# Lakota_PCB.net
KiCad netlist of a schematic drawn in Altium Designer
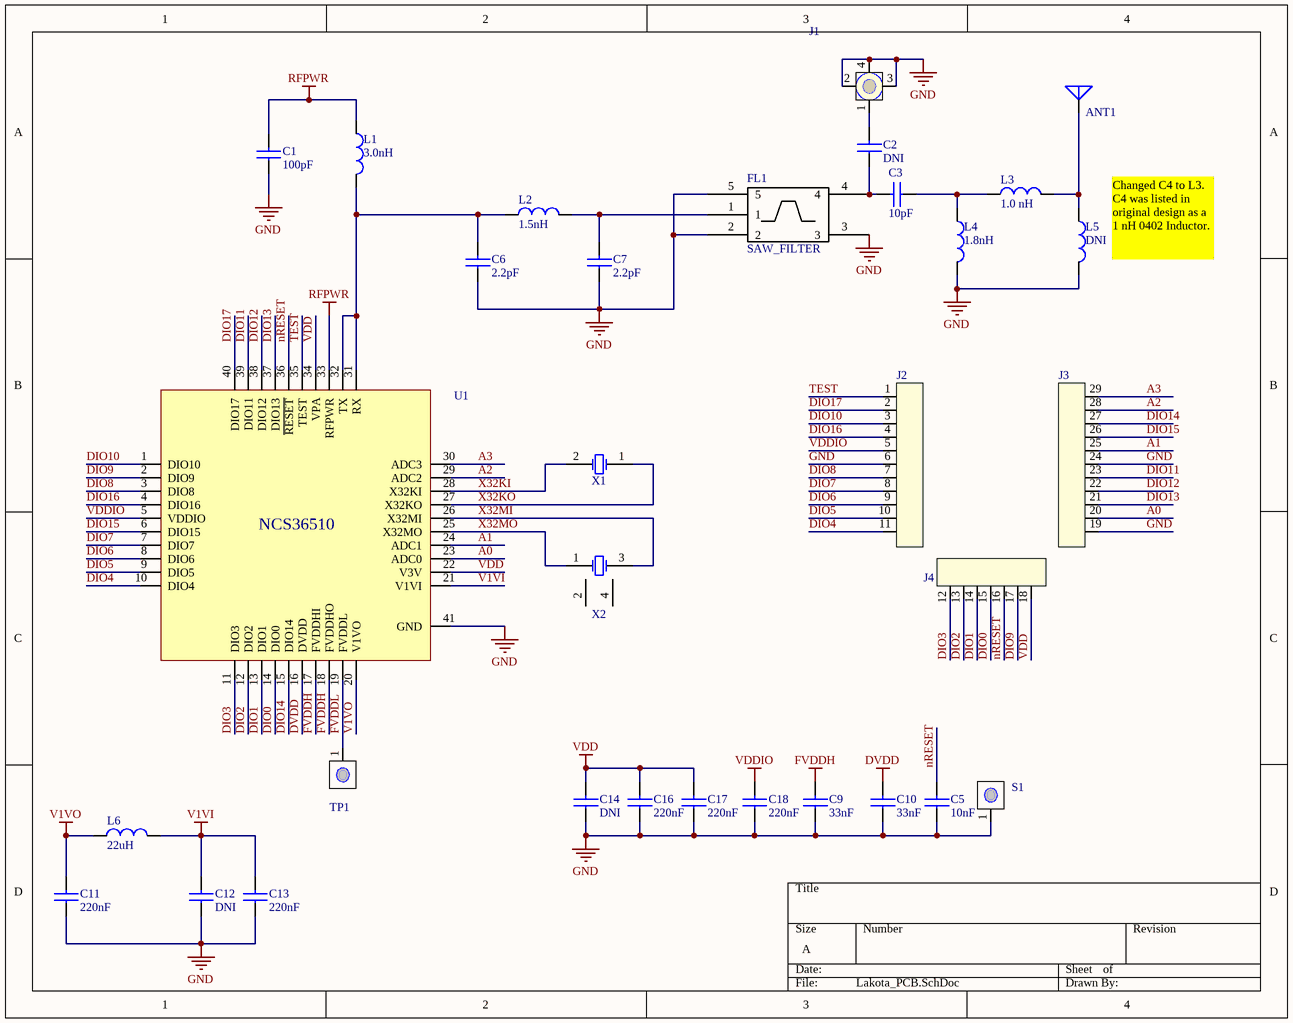
[diagram p0: Lakota_PCB.SchDoc]

(export (version "E")
  (design (tool "Eeschema 10.0.6"))
  (components
    (comp (ref "ANT1")
      (value "ANTENNA_JOHANSON_2450AT42A100_S")
      (footprint "JOHANSON_2450AT42A100_SMD")
      (libsource (lib "Lakota_PCB") (part "ANTENNA_0"))
    )
    (comp (ref "C1")
      (value "100pF")
      (footprint "C_0402")
      (fields (field (name "Comment") "CAPACITOR NON-POL_C_0402_100PF"))
      (libsource (lib "Lakota_PCB") (part "CAPACITOR_NP"))
    )
    (comp (ref "C2")
      (value "DNI")
      (footprint "C_0402_MOD1")
      (fields (field (name "Comment") "CAPACITOR NON-POL_C_0402_MOD1_D"))
      (libsource (lib "") (part "CAPACITOR_NP_1"))
    )
    (comp (ref "C3")
      (value "10pF")
      (footprint "C_0402_MOD1")
      (fields (field (name "Comment") "CAPACITOR NON-POL_C_0402_MOD1_1"))
      (libsource (lib "") (part "CAPACITOR_NP_1"))
    )
    (comp (ref "C5")
      (value "10nF")
      (footprint "C_0402")
      (fields (field (name "Comment") "CAPACITOR NON-POL_C_0402_10NF"))
      (libsource (lib "Lakota_PCB") (part "CAPACITOR_NP"))
    )
    (comp (ref "C6")
      (value "2.2pF")
      (footprint "C_0402")
      (fields (field (name "Comment") "CAPACITOR NON-POL_C_0402_DNI"))
      (libsource (lib "") (part "CAPACITOR_NP_1"))
    )
    (comp (ref "C7")
      (value "2.2pF")
      (footprint "C_0402")
      (fields (field (name "Comment") "CAPACITOR NON-POL_C_0402_DNI"))
      (libsource (lib "") (part "CAPACITOR_NP_1"))
    )
    (comp (ref "C9")
      (value "33nF")
      (footprint "C_0402")
      (fields (field (name "Comment") "CAPACITOR NON-POL_C_0402_33NF"))
      (libsource (lib "Lakota_PCB") (part "CAPACITOR_NP"))
    )
    (comp (ref "C10")
      (value "33nF")
      (footprint "C_0402")
      (fields (field (name "Comment") "CAPACITOR NON-POL_C_0402_33NF"))
      (libsource (lib "Lakota_PCB") (part "CAPACITOR_NP"))
    )
    (comp (ref "C11")
      (value "220nF")
      (footprint "C_0402")
      (fields (field (name "Comment") "CAPACITOR NON-POL_C_0402_220NF"))
      (libsource (lib "Lakota_PCB") (part "CAPACITOR_NP"))
    )
    (comp (ref "C12")
      (value "DNI")
      (footprint "C_0402")
      (fields (field (name "Comment") "CAPACITOR NON-POL_C_0402_220NF"))
      (libsource (lib "Lakota_PCB") (part "CAPACITOR_NP"))
    )
    (comp (ref "C13")
      (value "220nF")
      (footprint "C_0402")
      (fields (field (name "Comment") "CAPACITOR NON-POL_C_0402_DNI"))
      (libsource (lib "Lakota_PCB") (part "CAPACITOR_NP"))
    )
    (comp (ref "C14")
      (value "DNI")
      (footprint "C_0402")
      (fields (field (name "Comment") "CAPACITOR NON-POL_C_0402_DNI"))
      (libsource (lib "Lakota_PCB") (part "CAPACITOR_NP"))
    )
    (comp (ref "C16")
      (value "220nF")
      (footprint "C_0402")
      (fields (field (name "Comment") "CAPACITOR NON-POL_C_0402_220NF"))
      (libsource (lib "Lakota_PCB") (part "CAPACITOR_NP"))
    )
    (comp (ref "C17")
      (value "220nF")
      (footprint "C_0402")
      (fields (field (name "Comment") "CAPACITOR NON-POL_C_0402_220NF"))
      (libsource (lib "Lakota_PCB") (part "CAPACITOR_NP"))
    )
    (comp (ref "C18")
      (value "220nF")
      (footprint "C_0402")
      (fields (field (name "Comment") "CAPACITOR NON-POL_C_0402_220NF"))
      (libsource (lib "Lakota_PCB") (part "CAPACITOR_NP"))
    )
    (comp (ref "FL1")
      (value "SAW_FILTER")
      (footprint "SAW_FILTER")
      (description "SAW Filter")
      (libsource (lib "Lakota_PCB") (part "SAW_FILTER"))
    )
    (comp (ref "J1")
      (value "UFL_UFL_SMD_UFL")
      (footprint "UFL_SMD")
      (libsource (lib "Lakota_PCB") (part "CONN_UFL"))
    )
    (comp (ref "J2")
      (value "CONN_1_27MM_PITCH_PIN_1_11_11X1")
      (footprint "11X1MM_BOT_PAD_1_TO_11_SMD")
      (libsource (lib "Lakota_PCB") (part "CONN_1_27mm_pitch_pin_1_11"))
    )
    (comp (ref "J3")
      (value "CONN_1_27MM_PITCH_PIN_19_29_11X")
      (footprint "11X1MM_BOT_PAD_19_TO_29_SMD")
      (libsource (lib "Lakota_PCB") (part "CONN_1_27mm_pitch_pin_19_29"))
    )
    (comp (ref "J4")
      (value "CONN_1_27MM_PITCH_PIN_12_18_7X1")
      (footprint "7X1MM_BOT_PAD_12_TO_18_SMD")
      (libsource (lib "Lakota_PCB") (part "CONN_1_27mm_pitch_pin_12_18"))
    )
    (comp (ref "L1")
      (value "3.0nH")
      (footprint "L_0402")
      (fields (field (name "Comment") "INDUCTOR_L_0402_5.6NH"))
      (libsource (lib "Lakota_PCB") (part "INDUCTOR"))
    )
    (comp (ref "L2")
      (value "1.5nH")
      (footprint "L_0402")
      (fields (field (name "Comment") "INDUCTOR_L_0402_0R"))
      (libsource (lib "Lakota_PCB") (part "INDUCTOR"))
    )
    (comp (ref "L3")
      (value "1.0 nH")
      (footprint "L_0402")
      (fields (field (name "Comment") "CAPACITOR NON-POL_C_0402_0R"))
      (libsource (lib "") (part "INDUCTOR_1"))
    )
    (comp (ref "L4")
      (value "1.8nH")
      (footprint "L_0402")
      (fields (field (name "Comment") "INDUCTOR_L_0402_DNI"))
      (libsource (lib "Lakota_PCB") (part "INDUCTOR"))
    )
    (comp (ref "L5")
      (value "DNI")
      (footprint "L_0402")
      (fields (field (name "Comment") "INDUCTOR_L_0402_DNI"))
      (libsource (lib "Lakota_PCB") (part "INDUCTOR"))
    )
    (comp (ref "L6")
      (value "22uH")
      (footprint "L_0603")
      (fields (field (name "Comment") "INDUCTOR_L_0603_22UH"))
      (libsource (lib "Lakota_PCB") (part "INDUCTOR"))
    )
    (comp (ref "S1")
      (value "CON1_LAKOTA_SHIELD_SHIELD")
      (footprint "LAKOTA_SHIELD")
      (libsource (lib "Lakota_PCB") (part "SHIELD"))
    )
    (comp (ref "TP1")
      (value "CON1_TP-30C12_CON1")
      (footprint "TP-30C12")
      (libsource (lib "Lakota_PCB") (part "TESTPOINT"))
    )
    (comp (ref "U1")
      (value "NCS36510_NCS36510_NCS36510")
      (footprint "NCS36510")
      (libsource (lib "Lakota_PCB") (part "NCS36510"))
    )
    (comp (ref "X1")
      (value "CRYSTAL2/SM_HOSONIC_ETDG_20X12_")
      (footprint "HOSONIC_ETDG_20X12_SMD")
      (description "Crystal Oscillator")
      (libsource (lib "Lakota_PCB") (part "XTAL"))
    )
    (comp (ref "X2")
      (value "CRYSTAL4/SM_HOSONIC_2SB_250X200")
      (footprint "HOSONIC_2SB_250X200_SMD")
      (description "Crystal Oscillator")
      (libsource (lib "Lakota_PCB") (part "XTAL_4pin"))
    )
  )
  (nets
    (net (code "1") (name "/A0") (class "Default")
      (node (ref "J3") (pin "20") (pinfunction "20_20") (pintype "passive"))
      (node (ref "U1") (pin "23") (pinfunction "ADC0_23") (pintype "passive"))
    )
    (net (code "2") (name "/A1") (class "Default")
      (node (ref "J3") (pin "25") (pinfunction "25_25") (pintype "passive"))
      (node (ref "U1") (pin "24") (pinfunction "ADC1_24") (pintype "passive"))
    )
    (net (code "3") (name "/A2") (class "Default")
      (node (ref "J3") (pin "28") (pinfunction "28_28") (pintype "passive"))
      (node (ref "U1") (pin "29") (pinfunction "ADC2_29") (pintype "passive"))
    )
    (net (code "4") (name "/A3") (class "Default")
      (node (ref "J3") (pin "29") (pinfunction "29_29") (pintype "passive"))
      (node (ref "U1") (pin "30") (pinfunction "ADC3_30") (pintype "passive"))
    )
    (net (code "5") (name "/DIO0") (class "Default")
      (node (ref "J4") (pin "15") (pinfunction "15_15") (pintype "passive"))
      (node (ref "U1") (pin "14") (pinfunction "DIO0_14") (pintype "passive"))
    )
    (net (code "6") (name "/DIO1") (class "Default")
      (node (ref "J4") (pin "14") (pinfunction "14_14") (pintype "passive"))
      (node (ref "U1") (pin "13") (pinfunction "DIO1_13") (pintype "passive"))
    )
    (net (code "7") (name "/DIO2") (class "Default")
      (node (ref "J4") (pin "13") (pinfunction "13_13") (pintype "passive"))
      (node (ref "U1") (pin "12") (pinfunction "DIO2_12") (pintype "passive"))
    )
    (net (code "8") (name "/DIO3") (class "Default")
      (node (ref "J4") (pin "12") (pinfunction "12_12") (pintype "passive"))
      (node (ref "U1") (pin "11") (pinfunction "DIO3_11") (pintype "passive"))
    )
    (net (code "9") (name "/DIO4") (class "Default")
      (node (ref "J2") (pin "11") (pinfunction "11_11") (pintype "passive"))
      (node (ref "U1") (pin "10") (pinfunction "DIO4_10") (pintype "passive"))
    )
    (net (code "10") (name "/DIO5") (class "Default")
      (node (ref "J2") (pin "10") (pinfunction "10_10") (pintype "passive"))
      (node (ref "U1") (pin "9") (pinfunction "DIO5_9") (pintype "passive"))
    )
    (net (code "11") (name "/DIO6") (class "Default")
      (node (ref "J2") (pin "9") (pinfunction "9_9") (pintype "passive"))
      (node (ref "U1") (pin "8") (pinfunction "DIO6_8") (pintype "passive"))
    )
    (net (code "12") (name "/DIO7") (class "Default")
      (node (ref "J2") (pin "8") (pinfunction "8_8") (pintype "passive"))
      (node (ref "U1") (pin "7") (pinfunction "DIO7_7") (pintype "passive"))
    )
    (net (code "13") (name "/DIO8") (class "Default")
      (node (ref "J2") (pin "7") (pinfunction "7_7") (pintype "passive"))
      (node (ref "U1") (pin "3") (pinfunction "DIO8_3") (pintype "passive"))
    )
    (net (code "14") (name "/DIO9") (class "Default")
      (node (ref "J4") (pin "17") (pinfunction "17_17") (pintype "passive"))
      (node (ref "U1") (pin "2") (pinfunction "DIO9_2") (pintype "passive"))
    )
    (net (code "15") (name "/DIO10") (class "Default")
      (node (ref "J2") (pin "3") (pinfunction "3_3") (pintype "passive"))
      (node (ref "U1") (pin "1") (pinfunction "DIO10_1") (pintype "passive"))
    )
    (net (code "16") (name "/DIO11") (class "Default")
      (node (ref "J3") (pin "23") (pinfunction "23_23") (pintype "passive"))
      (node (ref "U1") (pin "39") (pinfunction "DIO11_39") (pintype "passive"))
    )
    (net (code "17") (name "/DIO12") (class "Default")
      (node (ref "J3") (pin "22") (pinfunction "22_22") (pintype "passive"))
      (node (ref "U1") (pin "38") (pinfunction "DIO12_38") (pintype "passive"))
    )
    (net (code "18") (name "/DIO13") (class "Default")
      (node (ref "J3") (pin "21") (pinfunction "21_21") (pintype "passive"))
      (node (ref "U1") (pin "37") (pinfunction "DIO13_37") (pintype "passive"))
    )
    (net (code "19") (name "/DIO14") (class "Default")
      (node (ref "J3") (pin "27") (pinfunction "27_27") (pintype "passive"))
      (node (ref "U1") (pin "15") (pinfunction "DIO14_15") (pintype "passive"))
    )
    (net (code "20") (name "/DIO15") (class "Default")
      (node (ref "J3") (pin "26") (pinfunction "26_26") (pintype "passive"))
      (node (ref "U1") (pin "6") (pinfunction "DIO15_6") (pintype "passive"))
    )
    (net (code "21") (name "/DIO16") (class "Default")
      (node (ref "J2") (pin "4") (pinfunction "4_4") (pintype "passive"))
      (node (ref "U1") (pin "4") (pinfunction "DIO16_4") (pintype "passive"))
    )
    (net (code "22") (name "/DIO17") (class "Default")
      (node (ref "J2") (pin "2") (pinfunction "2_2") (pintype "passive"))
      (node (ref "U1") (pin "40") (pinfunction "DIO17_40") (pintype "passive"))
    )
    (net (code "23") (name "/FVDDL") (class "Default")
      (node (ref "TP1") (pin "1") (pinfunction "1_1") (pintype "passive"))
      (node (ref "U1") (pin "19") (pinfunction "FVDDL_19") (pintype "passive"))
    )
    (net (code "24") (name "/TEST") (class "Default")
      (node (ref "J2") (pin "1") (pinfunction "1_1") (pintype "passive"))
      (node (ref "U1") (pin "35") (pinfunction "TEST_35") (pintype "passive"))
    )
    (net (code "25") (name "/X32KI") (class "Default")
      (node (ref "U1") (pin "28") (pinfunction "X32KI_28") (pintype "passive"))
      (node (ref "X1") (pin "2") (pinfunction "OSC2_2") (pintype "passive"))
    )
    (net (code "26") (name "/X32KO") (class "Default")
      (node (ref "U1") (pin "27") (pinfunction "X32KO_27") (pintype "passive"))
      (node (ref "X1") (pin "1") (pinfunction "OSC1_1") (pintype "passive"))
    )
    (net (code "27") (name "/X32MI") (class "Default")
      (node (ref "U1") (pin "26") (pinfunction "X32MI_26") (pintype "passive"))
      (node (ref "X2") (pin "3") (pinfunction "3_3") (pintype "passive"))
    )
    (net (code "28") (name "/X32MO") (class "Default")
      (node (ref "U1") (pin "25") (pinfunction "X32MO_25") (pintype "passive"))
      (node (ref "X2") (pin "1") (pinfunction "OSC1_1") (pintype "passive"))
    )
    (net (code "29") (name "/nRESET") (class "Default")
      (node (ref "C5") (pin "2") (pinfunction "2_2") (pintype "passive"))
      (node (ref "J4") (pin "16") (pinfunction "16_16") (pintype "passive"))
      (node (ref "U1") (pin "36") (pinfunction "~{RESET}_36") (pintype "passive"))
    )
    (net (code "30") (name "DVDD") (class "Default")
      (node (ref "C10") (pin "2") (pinfunction "2_2") (pintype "passive"))
      (node (ref "U1") (pin "16") (pinfunction "DVDD_16") (pintype "passive"))
    )
    (net (code "31") (name "FVDDH") (class "Default")
      (node (ref "C9") (pin "2") (pinfunction "2_2") (pintype "passive"))
      (node (ref "U1") (pin "17") (pinfunction "FVDDHI_17") (pintype "passive"))
      (node (ref "U1") (pin "18") (pinfunction "FVDDHO_18") (pintype "passive"))
    )
    (net (code "32") (name "GND") (class "Default")
      (node (ref "C1") (pin "1") (pinfunction "1_1") (pintype "passive"))
      (node (ref "C10") (pin "1") (pinfunction "1_1") (pintype "passive"))
      (node (ref "C11") (pin "1") (pinfunction "1_1") (pintype "passive"))
      (node (ref "C12") (pin "1") (pinfunction "1_1") (pintype "passive"))
      (node (ref "C13") (pin "1") (pinfunction "1_1") (pintype "passive"))
      (node (ref "C14") (pin "1") (pinfunction "1_1") (pintype "passive"))
      (node (ref "C16") (pin "1") (pinfunction "1_1") (pintype "passive"))
      (node (ref "C17") (pin "1") (pinfunction "1_1") (pintype "passive"))
      (node (ref "C18") (pin "1") (pinfunction "1_1") (pintype "passive"))
      (node (ref "C5") (pin "1") (pinfunction "1_1") (pintype "passive"))
      (node (ref "C6") (pin "2") (pinfunction "2_2") (pintype "passive"))
      (node (ref "C7") (pin "2") (pinfunction "2_2") (pintype "passive"))
      (node (ref "C9") (pin "1") (pinfunction "1_1") (pintype "passive"))
      (node (ref "FL1") (pin "2") (pinfunction "2_2") (pintype "passive"))
      (node (ref "FL1") (pin "3") (pinfunction "3_3") (pintype "passive"))
      (node (ref "FL1") (pin "5") (pinfunction "5_5") (pintype "passive"))
      (node (ref "J1") (pin "2") (pinfunction "2_2") (pintype "passive"))
      (node (ref "J1") (pin "3") (pinfunction "3_3") (pintype "passive"))
      (node (ref "J1") (pin "4") (pinfunction "4_4") (pintype "passive"))
      (node (ref "J2") (pin "6") (pinfunction "6_6") (pintype "passive"))
      (node (ref "J3") (pin "19") (pinfunction "19_19") (pintype "passive"))
      (node (ref "J3") (pin "24") (pinfunction "24_24") (pintype "passive"))
      (node (ref "L4") (pin "2") (pinfunction "2_2") (pintype "passive"))
      (node (ref "L5") (pin "2") (pinfunction "2_2") (pintype "passive"))
      (node (ref "S1") (pin "1") (pinfunction "1_1") (pintype "passive"))
      (node (ref "U1") (pin "41") (pinfunction "GND_41") (pintype "passive"))
    )
    (net (code "33") (name "Net-(ANT1-Pad1)") (class "Default")
      (node (ref "ANT1") (pin "1") (pinfunction "1_1") (pintype "passive"))
      (node (ref "L3") (pin "1") (pinfunction "1_1") (pintype "passive"))
      (node (ref "L5") (pin "1") (pinfunction "1_1") (pintype "passive"))
    )
    (net (code "34") (name "Net-(C2-Pad1)") (class "Default")
      (node (ref "C2") (pin "1") (pinfunction "1_1") (pintype "passive"))
      (node (ref "J1") (pin "1") (pinfunction "1_1") (pintype "passive"))
    )
    (net (code "35") (name "Net-(C2-Pad2)") (class "Default")
      (node (ref "C2") (pin "2") (pinfunction "2_2") (pintype "passive"))
      (node (ref "C3") (pin "1") (pinfunction "1_1") (pintype "passive"))
      (node (ref "FL1") (pin "4") (pinfunction "4_4") (pintype "passive"))
    )
    (net (code "36") (name "Net-(C3-Pad2)") (class "Default")
      (node (ref "C3") (pin "2") (pinfunction "2_2") (pintype "passive"))
      (node (ref "L3") (pin "2") (pinfunction "2_2") (pintype "passive"))
      (node (ref "L4") (pin "1") (pinfunction "1_1") (pintype "passive"))
    )
    (net (code "37") (name "Net-(C7-Pad1)") (class "Default")
      (node (ref "C7") (pin "1") (pinfunction "1_1") (pintype "passive"))
      (node (ref "FL1") (pin "1") (pinfunction "1_1") (pintype "passive"))
      (node (ref "L2") (pin "2") (pinfunction "2_2") (pintype "passive"))
    )
    (net (code "38") (name "Net-(U1-RX)") (class "Default")
      (node (ref "C6") (pin "1") (pinfunction "1_1") (pintype "passive"))
      (node (ref "L1") (pin "2") (pinfunction "2_2") (pintype "passive"))
      (node (ref "L2") (pin "1") (pinfunction "1_1") (pintype "passive"))
      (node (ref "U1") (pin "31") (pinfunction "RX_31") (pintype "passive"))
      (node (ref "U1") (pin "32") (pinfunction "TX_32") (pintype "passive"))
    )
    (net (code "39") (name "RFPWR") (class "Default")
      (node (ref "C1") (pin "2") (pinfunction "2_2") (pintype "passive"))
      (node (ref "L1") (pin "1") (pinfunction "1_1") (pintype "passive"))
      (node (ref "U1") (pin "33") (pinfunction "RFPWR_33") (pintype "passive"))
    )
    (net (code "40") (name "V1VI") (class "Default")
      (node (ref "C12") (pin "2") (pinfunction "2_2") (pintype "passive"))
      (node (ref "C13") (pin "2") (pinfunction "2_2") (pintype "passive"))
      (node (ref "L6") (pin "2") (pinfunction "2_2") (pintype "passive"))
      (node (ref "U1") (pin "21") (pinfunction "V1VI_21") (pintype "passive"))
    )
    (net (code "41") (name "V1VO") (class "Default")
      (node (ref "C11") (pin "2") (pinfunction "2_2") (pintype "passive"))
      (node (ref "L6") (pin "1") (pinfunction "1_1") (pintype "passive"))
      (node (ref "U1") (pin "20") (pinfunction "V1VO_20") (pintype "passive"))
    )
    (net (code "42") (name "VDD") (class "Default")
      (node (ref "C14") (pin "2") (pinfunction "2_2") (pintype "passive"))
      (node (ref "C16") (pin "2") (pinfunction "2_2") (pintype "passive"))
      (node (ref "C17") (pin "2") (pinfunction "2_2") (pintype "passive"))
      (node (ref "J4") (pin "18") (pinfunction "18_18") (pintype "passive"))
      (node (ref "U1") (pin "22") (pinfunction "V3V_22") (pintype "passive"))
      (node (ref "U1") (pin "34") (pinfunction "VPA_34") (pintype "passive"))
    )
    (net (code "43") (name "VDDIO") (class "Default")
      (node (ref "C18") (pin "2") (pinfunction "2_2") (pintype "passive"))
      (node (ref "J2") (pin "5") (pinfunction "5_5") (pintype "passive"))
      (node (ref "U1") (pin "5") (pinfunction "VDDIO_5") (pintype "passive"))
    )
    (net (code "44") (name "unconnected-(X2-OSC2-Pad2)") (class "Default")
      (node (ref "X2") (pin "2") (pinfunction "OSC2_2") (pintype "passive"))
    )
    (net (code "45") (name "unconnected-(X2-OSC4-Pad4)") (class "Default")
      (node (ref "X2") (pin "4") (pinfunction "OSC4_4") (pintype "passive"))
    )
  )
)
